# MICROSD.net
KiCad netlist of a schematic drawn in Altium Designer
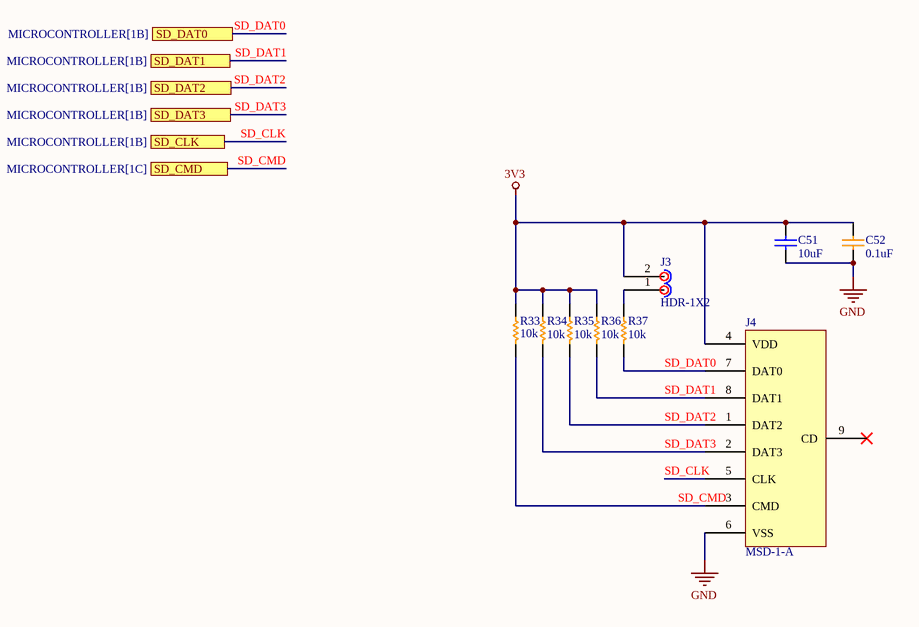
[diagram p0: MICROSD.SchDoc]

(export (version "E")
  (design (tool "Eeschema 10.0.6"))
  (components
    (comp (ref "C51")
      (value "10uF")
      (footprint "CAP-0805")
      (description "CAP CER 22UF 10V X5R 0805")
      (libsource (lib "Schlib1") (part "CAP-0805"))
    )
    (comp (ref "C52")
      (value "0.1uF")
      (footprint "CAP-0603")
      (description "CAP CER 0.1UF 10V X7R 0603")
      (libsource (lib "Schlib1") (part "CAP-0603"))
    )
    (comp (ref "J3") (value "HDR-1X2") (footprint "HDR-1X2") (libsource (lib "schematic") (part "HDR-1X2")))
    (comp (ref "J4")
      (value "MSD-1-A")
      (footprint "MSD-1-A")
      (description "CONN MICROSD CARD R/A SMD")
      (libsource (lib "schematic") (part "MSD-1-A"))
    )
    (comp (ref "R33")
      (value "10k")
      (footprint "RES-0603")
      (description "RES SMD 10K OHM 1% 1/10W 0603")
      (libsource (lib "Schlib1") (part "RES-0603"))
    )
    (comp (ref "R34")
      (value "10k")
      (footprint "RES-0603")
      (description "RES SMD 10K OHM 1% 1/10W 0603")
      (libsource (lib "Schlib1") (part "RES-0603"))
    )
    (comp (ref "R35")
      (value "10k")
      (footprint "RES-0603")
      (description "RES SMD 10K OHM 1% 1/10W 0603")
      (libsource (lib "Schlib1") (part "RES-0603"))
    )
    (comp (ref "R36")
      (value "10k")
      (footprint "RES-0603")
      (description "RES SMD 10K OHM 1% 1/10W 0603")
      (libsource (lib "Schlib1") (part "RES-0603"))
    )
    (comp (ref "R37")
      (value "10k")
      (footprint "RES-0603")
      (description "RES SMD 10K OHM 1% 1/10W 0603")
      (libsource (lib "Schlib1") (part "RES-0603"))
    )
  )
  (nets
    (net (code "1") (name "/SD_CLK") (class "Default")
      (node (ref "J4") (pin "5") (pinfunction "CLK_5") (pintype "passive"))
    )
    (net (code "2") (name "/SD_CMD") (class "Default")
      (node (ref "J4") (pin "3") (pinfunction "CMD_3") (pintype "passive"))
      (node (ref "R33") (pin "1") (pinfunction "1_1") (pintype "passive"))
    )
    (net (code "3") (name "/SD_DAT0") (class "Default")
      (node (ref "J4") (pin "7") (pinfunction "DAT0_7") (pintype "power_in"))
      (node (ref "R37") (pin "1") (pinfunction "1_1") (pintype "passive"))
    )
    (net (code "4") (name "/SD_DAT1") (class "Default")
      (node (ref "J4") (pin "8") (pinfunction "DAT1_8") (pintype "passive"))
      (node (ref "R36") (pin "1") (pinfunction "1_1") (pintype "passive"))
    )
    (net (code "5") (name "/SD_DAT2") (class "Default")
      (node (ref "J4") (pin "1") (pinfunction "DAT2_1") (pintype "passive"))
      (node (ref "R35") (pin "1") (pinfunction "1_1") (pintype "passive"))
    )
    (net (code "6") (name "/SD_DAT3") (class "Default")
      (node (ref "J4") (pin "2") (pinfunction "DAT3_2") (pintype "passive"))
      (node (ref "R34") (pin "1") (pinfunction "1_1") (pintype "passive"))
    )
    (net (code "7") (name "3V3") (class "Default")
      (node (ref "C51") (pin "2") (pinfunction "2_2") (pintype "passive"))
      (node (ref "C52") (pin "2") (pinfunction "2_2") (pintype "passive"))
      (node (ref "J3") (pin "2") (pintype "passive"))
      (node (ref "J4") (pin "4") (pinfunction "VDD_4") (pintype "passive"))
      (node (ref "R33") (pin "2") (pinfunction "2_2") (pintype "passive"))
      (node (ref "R34") (pin "2") (pinfunction "2_2") (pintype "passive"))
      (node (ref "R35") (pin "2") (pinfunction "2_2") (pintype "passive"))
      (node (ref "R36") (pin "2") (pinfunction "2_2") (pintype "passive"))
    )
    (net (code "8") (name "GND") (class "Default")
      (node (ref "C51") (pin "1") (pinfunction "1_1") (pintype "passive"))
      (node (ref "C52") (pin "1") (pinfunction "1_1") (pintype "passive"))
      (node (ref "J4") (pin "6") (pinfunction "VSS_6") (pintype "passive"))
    )
    (net (code "9") (name "Net-(J3-Pad1)") (class "Default")
      (node (ref "J3") (pin "1") (pintype "passive"))
      (node (ref "R37") (pin "2") (pinfunction "2_2") (pintype "passive"))
    )
    (net (code "10") (name "unconnected-(J4-CD-Pad9)") (class "Default")
      (node (ref "J4") (pin "9") (pinfunction "CD_9") (pintype "passive+no_connect"))
    )
  )
)
